# FLC100_level_shifting_mag.net
KiCad netlist of a schematic drawn in EAGLE
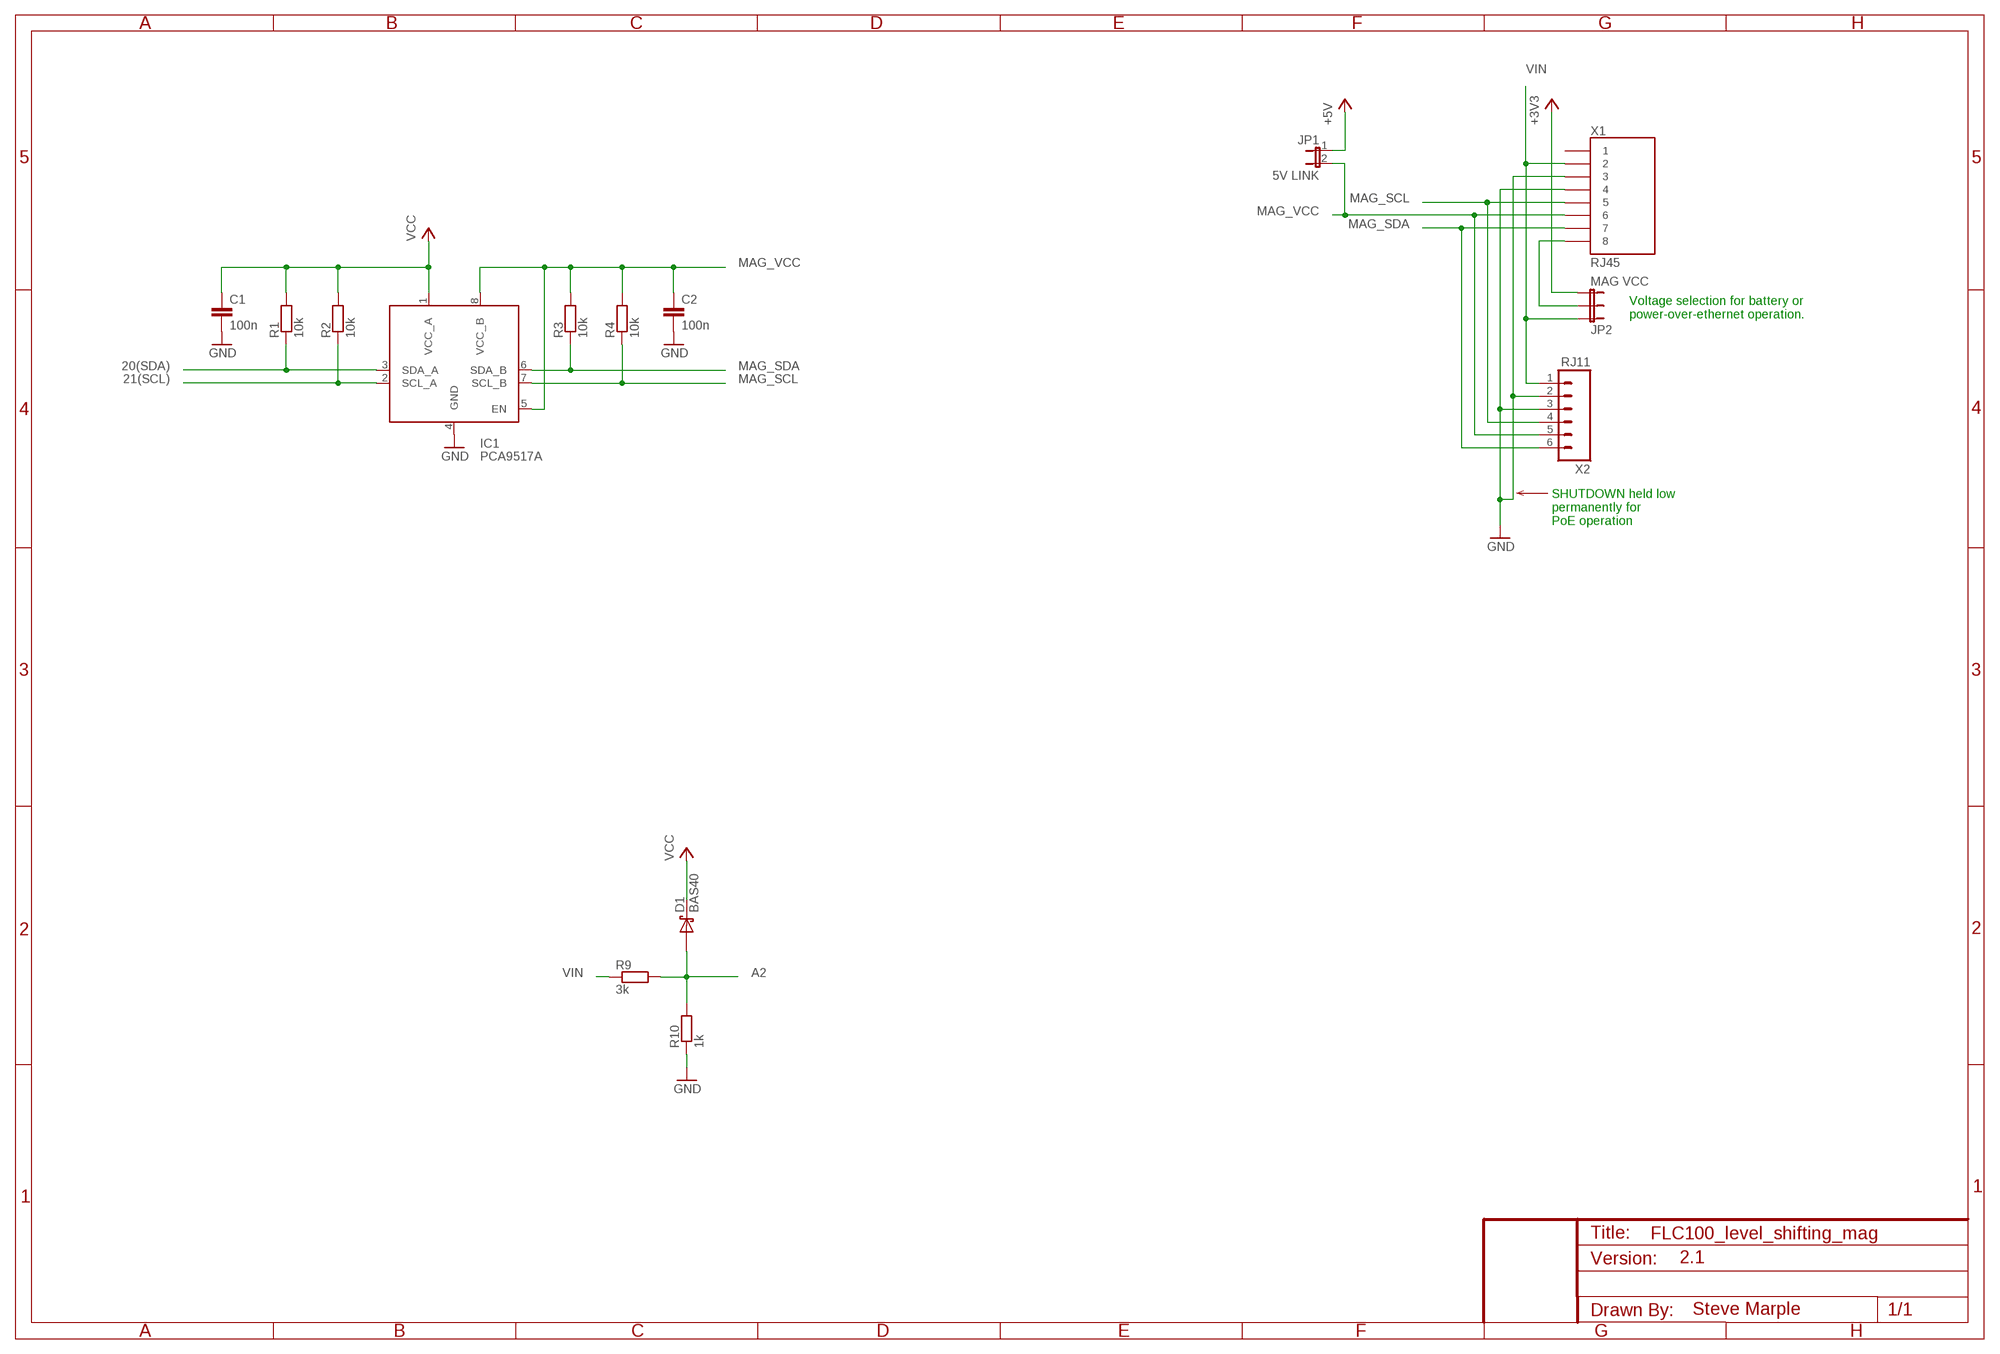
[diagram p0: schematic, sheet 1]

(export (version "E")
  (design (tool "Eeschema 10.0.6"))
  (components
    (comp (ref "C1")
      (value "100n")
      (footprint "eagle-import:1206-HAND")
      (libsource (lib "eagle-import") (part "C-EU1206-HAND"))
    )
    (comp (ref "C2")
      (value "100n")
      (footprint "eagle-import:1206-HAND")
      (libsource (lib "eagle-import") (part "C-EU1206-HAND"))
    )
    (comp (ref "D1")
      (value "BAS40")
      (footprint "eagle-import:SOT23-3-HAND")
      (libsource (lib "eagle-import") (part "DIODE-SCHOTTKYSOT23-1-3-HAND"))
    )
    (comp (ref "IC1")
      (value "PCA9517A")
      (footprint "eagle-import:SO08")
      (libsource (lib "eagle-import") (part "PCA9517ASOIC"))
    )
    (comp (ref "JP1")
      (value "5V LINK")
      (footprint "eagle-import:1X02")
      (libsource (lib "eagle-import") (part "JUMPER-2PTH"))
    )
    (comp (ref "JP2")
      (value "MAG VCC")
      (footprint "eagle-import:1X03")
      (libsource (lib "eagle-import") (part "JUMPER-3PTH"))
    )
    (comp (ref "R1")
      (value "10k")
      (footprint "eagle-import:1206-HAND")
      (libsource (lib "eagle-import") (part "RESISTOR1206-HAND"))
    )
    (comp (ref "R2")
      (value "10k")
      (footprint "eagle-import:1206-HAND")
      (libsource (lib "eagle-import") (part "RESISTOR1206-HAND"))
    )
    (comp (ref "R3")
      (value "10k")
      (footprint "eagle-import:1206-HAND")
      (libsource (lib "eagle-import") (part "RESISTOR1206-HAND"))
    )
    (comp (ref "R4")
      (value "10k")
      (footprint "eagle-import:1206-HAND")
      (libsource (lib "eagle-import") (part "RESISTOR1206-HAND"))
    )
    (comp (ref "R9")
      (value "3k")
      (footprint "eagle-import:1206-HAND")
      (libsource (lib "eagle-import") (part "RESISTOR1206-HAND"))
    )
    (comp (ref "R10")
      (value "1k")
      (footprint "eagle-import:1206-HAND")
      (libsource (lib "eagle-import") (part "RESISTOR1206-HAND"))
    )
    (comp (ref "X1")
      (value "RJ45")
      (footprint "eagle-import:RJ45-8")
      (libsource (lib "eagle-import") (part "RJ45-8PTH"))
    )
    (comp (ref "X2")
      (value "RJ11")
      (footprint "eagle-import:RJ11-6")
      (libsource (lib "eagle-import") (part "RJ11-6PTH"))
    )
  )
  (nets
    (net (code "1") (name "+3V3") (class "Default")
      (node (ref "JP2") (pin "3") (pinfunction "3_3") (pintype "passive"))
    )
    (net (code "2") (name "+5V") (class "Default")
      (node (ref "JP1") (pin "1") (pinfunction "1_1") (pintype "passive"))
    )
    (net (code "3") (name "/20(SDA)") (class "Default")
      (node (ref "IC1") (pin "3") (pinfunction "SDA_A_3") (pintype "bidirectional"))
      (node (ref "R1") (pin "1") (pinfunction "1_1") (pintype "passive"))
    )
    (net (code "4") (name "/21(SCL)") (class "Default")
      (node (ref "IC1") (pin "2") (pinfunction "SCL_A_2") (pintype "bidirectional"))
      (node (ref "R2") (pin "1") (pinfunction "1_1") (pintype "passive"))
    )
    (net (code "5") (name "/A2") (class "Default")
      (node (ref "D1") (pin "1") (pinfunction "A_1") (pintype "passive"))
      (node (ref "R10") (pin "2") (pinfunction "2_2") (pintype "passive"))
      (node (ref "R9") (pin "2") (pinfunction "2_2") (pintype "passive"))
    )
    (net (code "6") (name "/MAG_SCL") (class "Default")
      (node (ref "IC1") (pin "7") (pinfunction "SCL_B_7") (pintype "bidirectional"))
      (node (ref "R4") (pin "1") (pinfunction "1_1") (pintype "passive"))
      (node (ref "X1") (pin "5") (pinfunction "5_5") (pintype "bidirectional"))
      (node (ref "X2") (pin "4") (pinfunction "4_4") (pintype "passive"))
    )
    (net (code "7") (name "/MAG_SDA") (class "Default")
      (node (ref "IC1") (pin "6") (pinfunction "SDA_B_6") (pintype "bidirectional"))
      (node (ref "R3") (pin "1") (pinfunction "1_1") (pintype "passive"))
      (node (ref "X1") (pin "7") (pinfunction "7_7") (pintype "bidirectional"))
      (node (ref "X2") (pin "6") (pinfunction "6_6") (pintype "passive"))
    )
    (net (code "8") (name "/MAG_VCC") (class "Default")
      (node (ref "C2") (pin "1") (pinfunction "1_1") (pintype "passive"))
      (node (ref "IC1") (pin "5") (pinfunction "EN_5") (pintype "bidirectional"))
      (node (ref "IC1") (pin "8") (pinfunction "VCC_B_8") (pintype "power_in"))
      (node (ref "JP1") (pin "2") (pinfunction "2_2") (pintype "passive"))
      (node (ref "R3") (pin "2") (pinfunction "2_2") (pintype "passive"))
      (node (ref "R4") (pin "2") (pinfunction "2_2") (pintype "passive"))
      (node (ref "X1") (pin "6") (pinfunction "6_6") (pintype "bidirectional"))
      (node (ref "X2") (pin "5") (pinfunction "5_5") (pintype "passive"))
    )
    (net (code "9") (name "/VIN") (class "Default")
      (node (ref "JP2") (pin "1") (pinfunction "1_1") (pintype "passive"))
      (node (ref "R9") (pin "1") (pinfunction "1_1") (pintype "passive"))
      (node (ref "X1") (pin "2") (pinfunction "2_2") (pintype "bidirectional"))
      (node (ref "X2") (pin "1") (pinfunction "1_1") (pintype "passive"))
    )
    (net (code "10") (name "GND") (class "Default")
      (node (ref "C1") (pin "2") (pinfunction "2_2") (pintype "passive"))
      (node (ref "C2") (pin "2") (pinfunction "2_2") (pintype "passive"))
      (node (ref "IC1") (pin "4") (pinfunction "GND_4") (pintype "power_in"))
      (node (ref "R10") (pin "1") (pinfunction "1_1") (pintype "passive"))
      (node (ref "X1") (pin "3") (pinfunction "3_3") (pintype "bidirectional"))
      (node (ref "X1") (pin "4") (pinfunction "4_4") (pintype "bidirectional"))
      (node (ref "X2") (pin "2") (pinfunction "2_2") (pintype "passive"))
      (node (ref "X2") (pin "3") (pinfunction "3_3") (pintype "passive"))
    )
    (net (code "11") (name "Net-(JP2-Pad2)") (class "Default")
      (node (ref "JP2") (pin "2") (pinfunction "2_2") (pintype "passive"))
      (node (ref "X1") (pin "8") (pinfunction "8_8") (pintype "bidirectional"))
    )
    (net (code "12") (name "VCC") (class "Default")
      (node (ref "C1") (pin "1") (pinfunction "1_1") (pintype "passive"))
      (node (ref "D1") (pin "3") (pinfunction "C_3") (pintype "passive"))
      (node (ref "IC1") (pin "1") (pinfunction "VCC_A_1") (pintype "power_in"))
      (node (ref "R1") (pin "2") (pinfunction "2_2") (pintype "passive"))
      (node (ref "R2") (pin "2") (pinfunction "2_2") (pintype "passive"))
    )
    (net (code "13") (name "unconnected-(X1-Pad1)") (class "Default")
      (node (ref "X1") (pin "1") (pinfunction "1_1") (pintype "bidirectional"))
    )
  )
)
